# Sheet1.net
KiCad netlist of a schematic drawn in Altium Designer
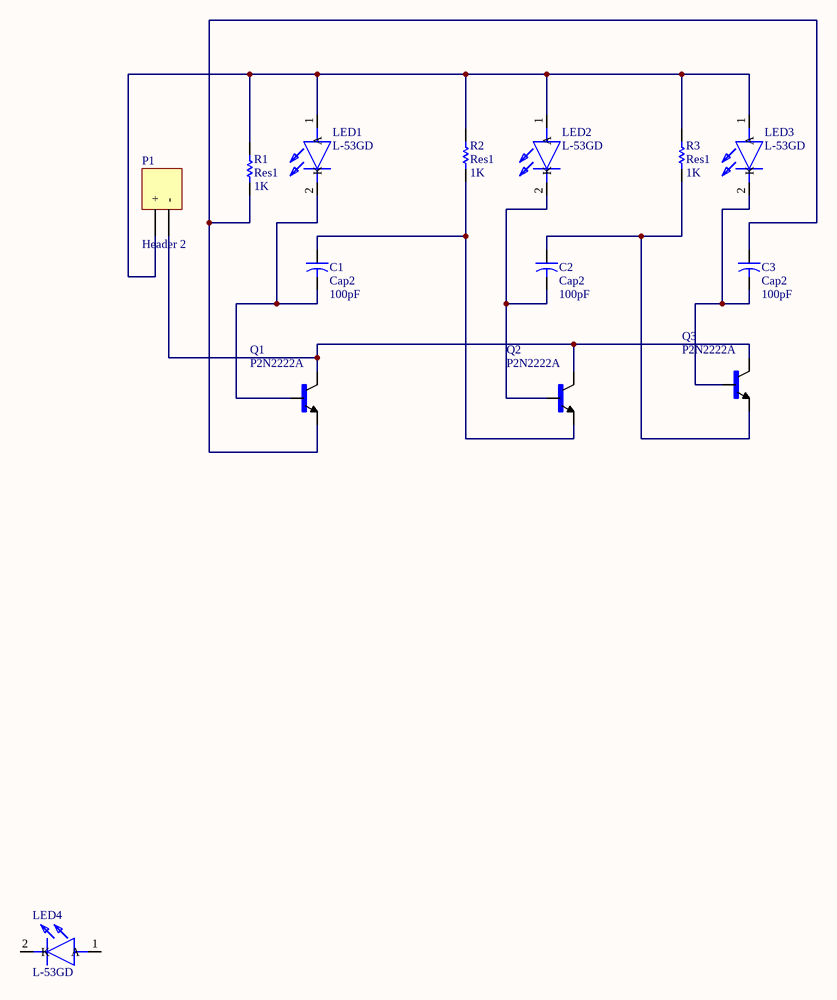
[diagram p0: Sheet1.SchDoc]

(export (version "E")
  (design (tool "Eeschema 10.0.6"))
  (components
    (comp (ref "C1")
      (value "Cap2")
      (footprint "CAPR5-4X5")
      (description "Capacitor")
      (fields (field (name "ALTIUM_VALUE") "100pF") (field (name "PUBLISHER") "Altium Limited"))
      (libsource (lib "Miscellaneous Devices") (part "Cap2"))
    )
    (comp (ref "C2")
      (value "Cap2")
      (footprint "CAPR5-4X5")
      (description "Capacitor")
      (fields (field (name "ALTIUM_VALUE") "100pF") (field (name "PUBLISHER") "Altium Limited"))
      (libsource (lib "Miscellaneous Devices") (part "Cap2"))
    )
    (comp (ref "C3")
      (value "Cap2")
      (footprint "CAPR5-4X5")
      (description "Capacitor")
      (fields (field (name "ALTIUM_VALUE") "100pF") (field (name "PUBLISHER") "Altium Limited"))
      (libsource (lib "Miscellaneous Devices") (part "Cap2"))
    )
    (comp (ref "LED1")
      (value "L-53GD")
      (footprint "SamacSys:L-53GD")
      (description "LED")
      (fields (field (name "RS PART NUMBER") "2286004A"))
      (libsource (lib "SamacSys") (part "L-53GD"))
    )
    (comp (ref "LED2")
      (value "L-53GD")
      (footprint "SamacSys:L-53GD")
      (description "LED")
      (fields (field (name "RS PART NUMBER") "2286004A"))
      (libsource (lib "SamacSys") (part "L-53GD"))
    )
    (comp (ref "LED3")
      (value "L-53GD")
      (footprint "SamacSys:L-53GD")
      (description "LED")
      (fields (field (name "RS PART NUMBER") "2286004A"))
      (libsource (lib "SamacSys") (part "L-53GD"))
    )
    (comp (ref "LED4")
      (value "L-53GD")
      (footprint "SamacSys:L-53GD")
      (description "LED")
      (fields (field (name "RS PART NUMBER") "2286004A"))
      (libsource (lib "*") (part "L-53GD"))
    )
    (comp (ref "P1")
      (value "Header 2")
      (footprint "HDR1X2")
      (description "Header, 2-Pin")
      (fields (field (name "PUBLISHER") "Altium Limited"))
      (libsource (lib "Miscellaneous Connectors") (part "Header 2"))
    )
    (comp (ref "Q1")
      (value "P2N2222A")
      (footprint "*TO92")
      (fields (field (name "MF") "ON Semiconductor"))
      (libsource (lib "P2N2222A") (part "P2N2222A"))
    )
    (comp (ref "Q2")
      (value "P2N2222A")
      (footprint "*TO92")
      (fields (field (name "MF") "ON Semiconductor"))
      (libsource (lib "P2N2222A") (part "P2N2222A"))
    )
    (comp (ref "Q3")
      (value "P2N2222A")
      (footprint "*TO92")
      (fields (field (name "MF") "ON Semiconductor"))
      (libsource (lib "P2N2222A") (part "P2N2222A"))
    )
    (comp (ref "R1")
      (value "Res1")
      (footprint "AXIAL-0.3")
      (description "Resistor")
      (fields (field (name "ALTIUM_VALUE") "1K") (field (name "PUBLISHER") "Altium Limited"))
      (libsource (lib "Miscellaneous Devices") (part "Res1"))
    )
    (comp (ref "R2")
      (value "Res1")
      (footprint "AXIAL-0.3")
      (description "Resistor")
      (fields (field (name "ALTIUM_VALUE") "1K") (field (name "PUBLISHER") "Altium Limited"))
      (libsource (lib "Miscellaneous Devices") (part "Res1"))
    )
    (comp (ref "R3")
      (value "Res1")
      (footprint "AXIAL-0.3")
      (description "Resistor")
      (fields (field (name "ALTIUM_VALUE") "1K") (field (name "PUBLISHER") "Altium Limited"))
      (libsource (lib "Miscellaneous Devices") (part "Res1"))
    )
  )
  (nets
    (net (code "1") (name "Net-(LED1-A)") (class "Default")
      (node (ref "LED1") (pin "1") (pinfunction "A_1") (pintype "passive"))
      (node (ref "LED2") (pin "1") (pinfunction "A_1") (pintype "passive"))
      (node (ref "LED3") (pin "1") (pinfunction "A_1") (pintype "passive"))
      (node (ref "P1") (pin "1") (pinfunction "+_1") (pintype "passive"))
      (node (ref "R1") (pin "2") (pinfunction "2_2") (pintype "passive"))
      (node (ref "R2") (pin "2") (pinfunction "2_2") (pintype "passive"))
      (node (ref "R3") (pin "2") (pinfunction "2_2") (pintype "passive"))
    )
    (net (code "2") (name "Net-(LED1-K)") (class "Default")
      (node (ref "C1") (pin "2") (pinfunction "2_2") (pintype "passive"))
      (node (ref "LED1") (pin "2") (pinfunction "K_2") (pintype "passive"))
      (node (ref "Q1") (pin "2") (pinfunction "B_2") (pintype "passive"))
    )
    (net (code "3") (name "Net-(LED2-K)") (class "Default")
      (node (ref "C2") (pin "2") (pinfunction "2_2") (pintype "passive"))
      (node (ref "LED2") (pin "2") (pinfunction "K_2") (pintype "passive"))
      (node (ref "Q2") (pin "2") (pinfunction "B_2") (pintype "passive"))
    )
    (net (code "4") (name "Net-(LED3-K)") (class "Default")
      (node (ref "C3") (pin "2") (pinfunction "2_2") (pintype "passive"))
      (node (ref "LED3") (pin "2") (pinfunction "K_2") (pintype "passive"))
      (node (ref "Q3") (pin "2") (pinfunction "B_2") (pintype "passive"))
    )
    (net (code "5") (name "Net-(P1--)") (class "Default")
      (node (ref "P1") (pin "2") (pinfunction "-_2") (pintype "passive"))
      (node (ref "Q1") (pin "3") (pinfunction "C_3") (pintype "passive"))
      (node (ref "Q2") (pin "3") (pinfunction "C_3") (pintype "passive"))
      (node (ref "Q3") (pin "3") (pinfunction "C_3") (pintype "passive"))
    )
    (net (code "6") (name "Net-(Q1-E)") (class "Default")
      (node (ref "C3") (pin "1") (pinfunction "1_1") (pintype "passive"))
      (node (ref "Q1") (pin "1") (pinfunction "E_1") (pintype "passive"))
      (node (ref "R1") (pin "1") (pinfunction "1_1") (pintype "passive"))
    )
    (net (code "7") (name "Net-(Q2-E)") (class "Default")
      (node (ref "C1") (pin "1") (pinfunction "1_1") (pintype "passive"))
      (node (ref "Q2") (pin "1") (pinfunction "E_1") (pintype "passive"))
      (node (ref "R2") (pin "1") (pinfunction "1_1") (pintype "passive"))
    )
    (net (code "8") (name "Net-(Q3-E)") (class "Default")
      (node (ref "C2") (pin "1") (pinfunction "1_1") (pintype "passive"))
      (node (ref "Q3") (pin "1") (pinfunction "E_1") (pintype "passive"))
      (node (ref "R3") (pin "1") (pinfunction "1_1") (pintype "passive"))
    )
    (net (code "9") (name "unconnected-(LED4-A-Pad1)") (class "Default")
      (node (ref "LED4") (pin "1") (pinfunction "A_1") (pintype "passive"))
    )
    (net (code "10") (name "unconnected-(LED4-K-Pad2)") (class "Default")
      (node (ref "LED4") (pin "2") (pinfunction "K_2") (pintype "passive"))
    )
  )
)
